# seq__control_pad_03.net
KiCad netlist of a schematic drawn in EAGLE
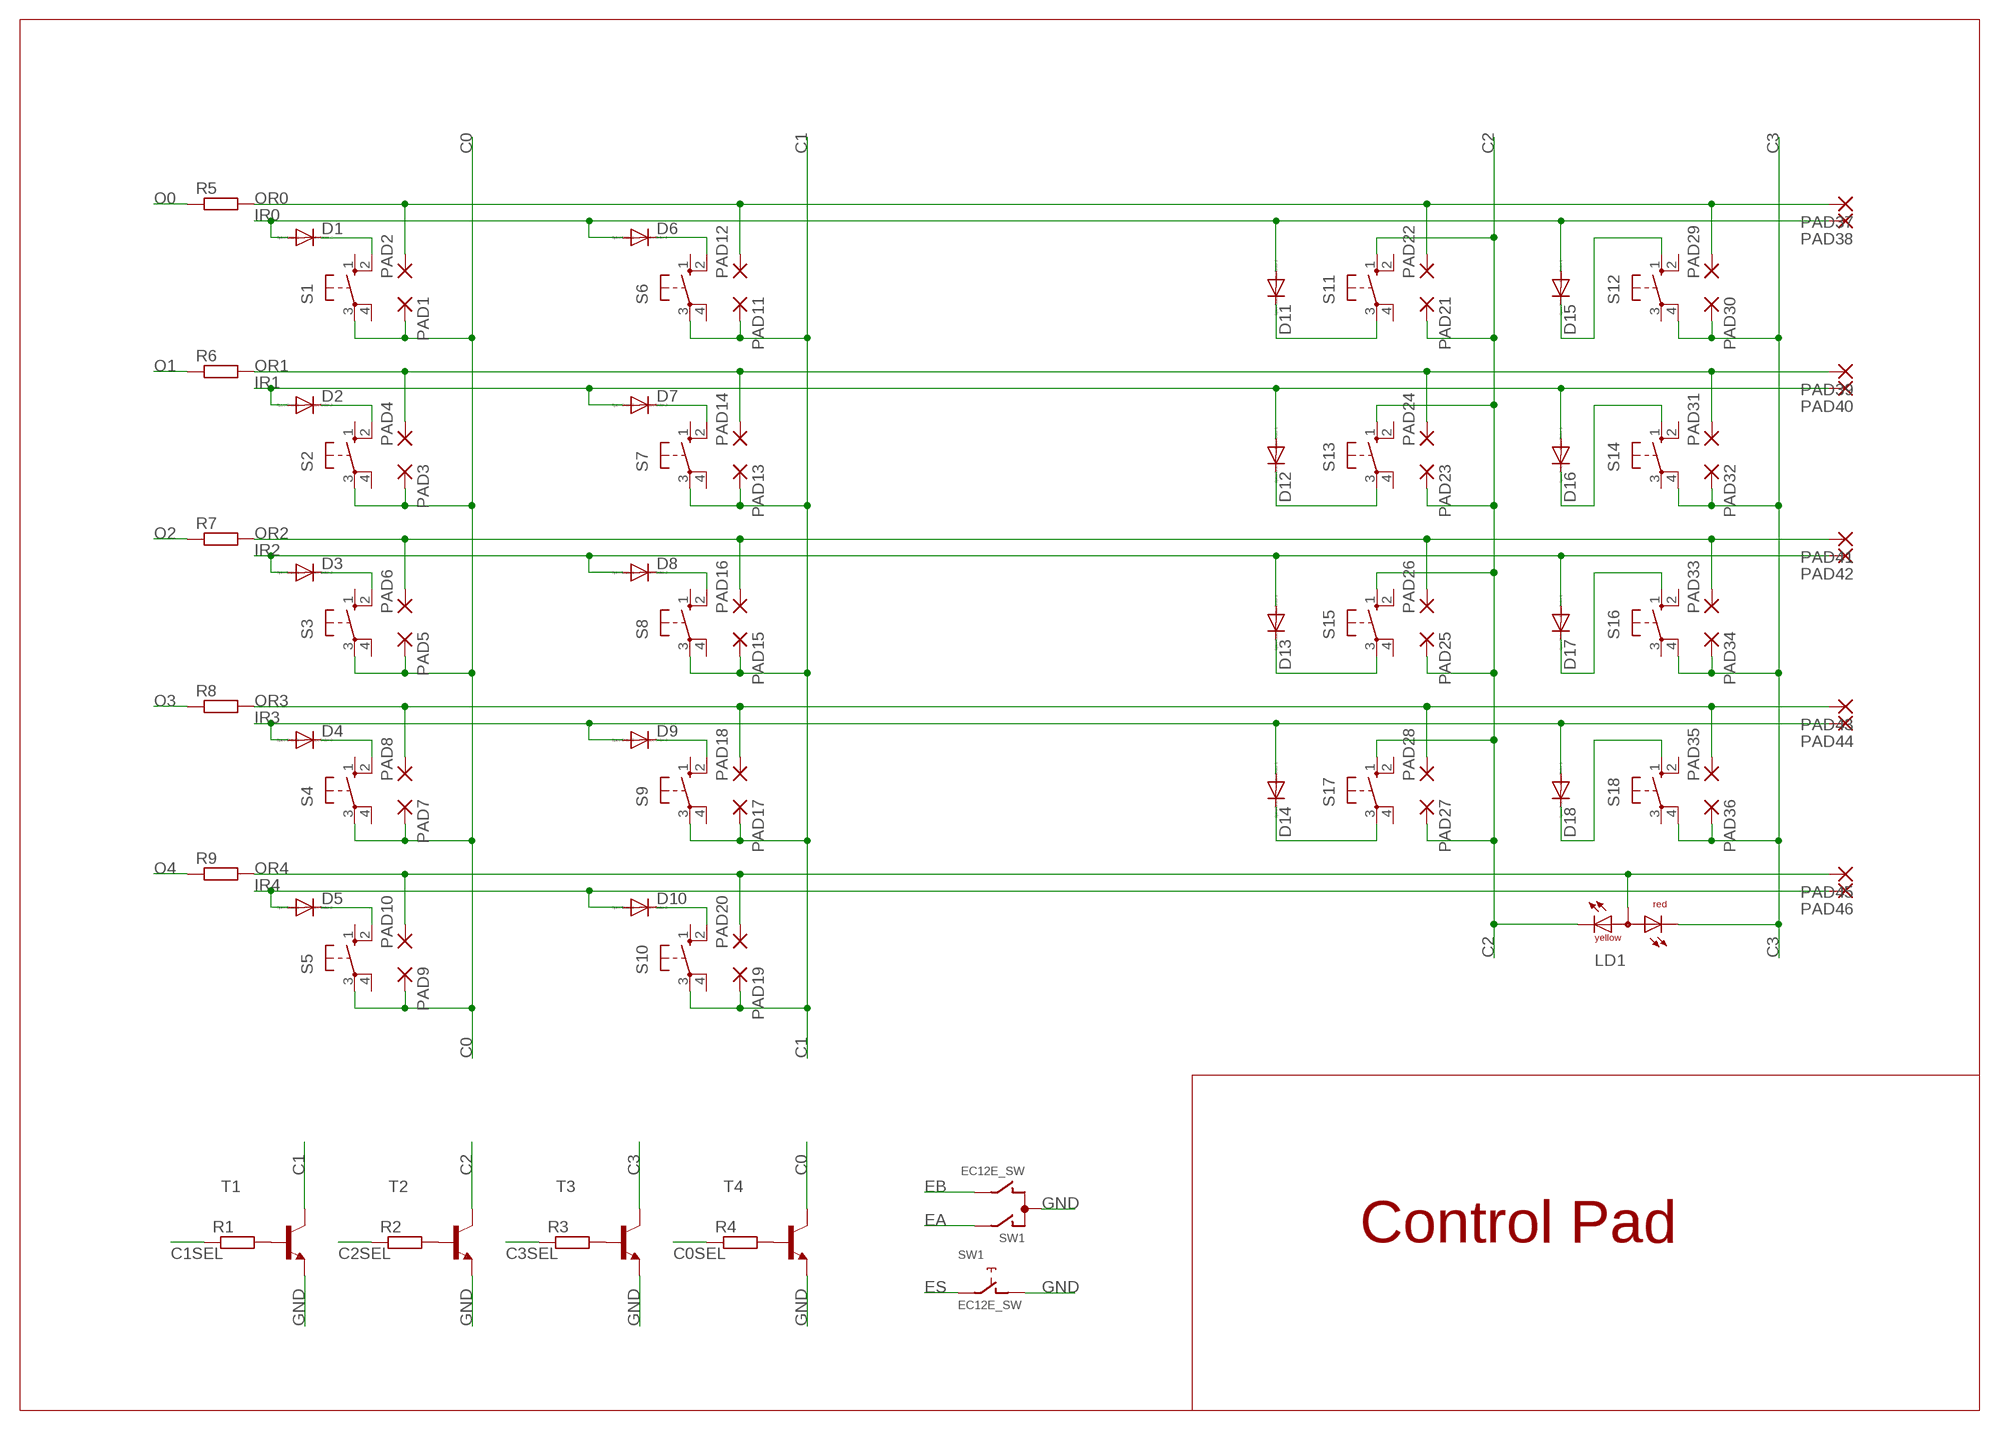
[diagram p0: schematic, sheet 1]
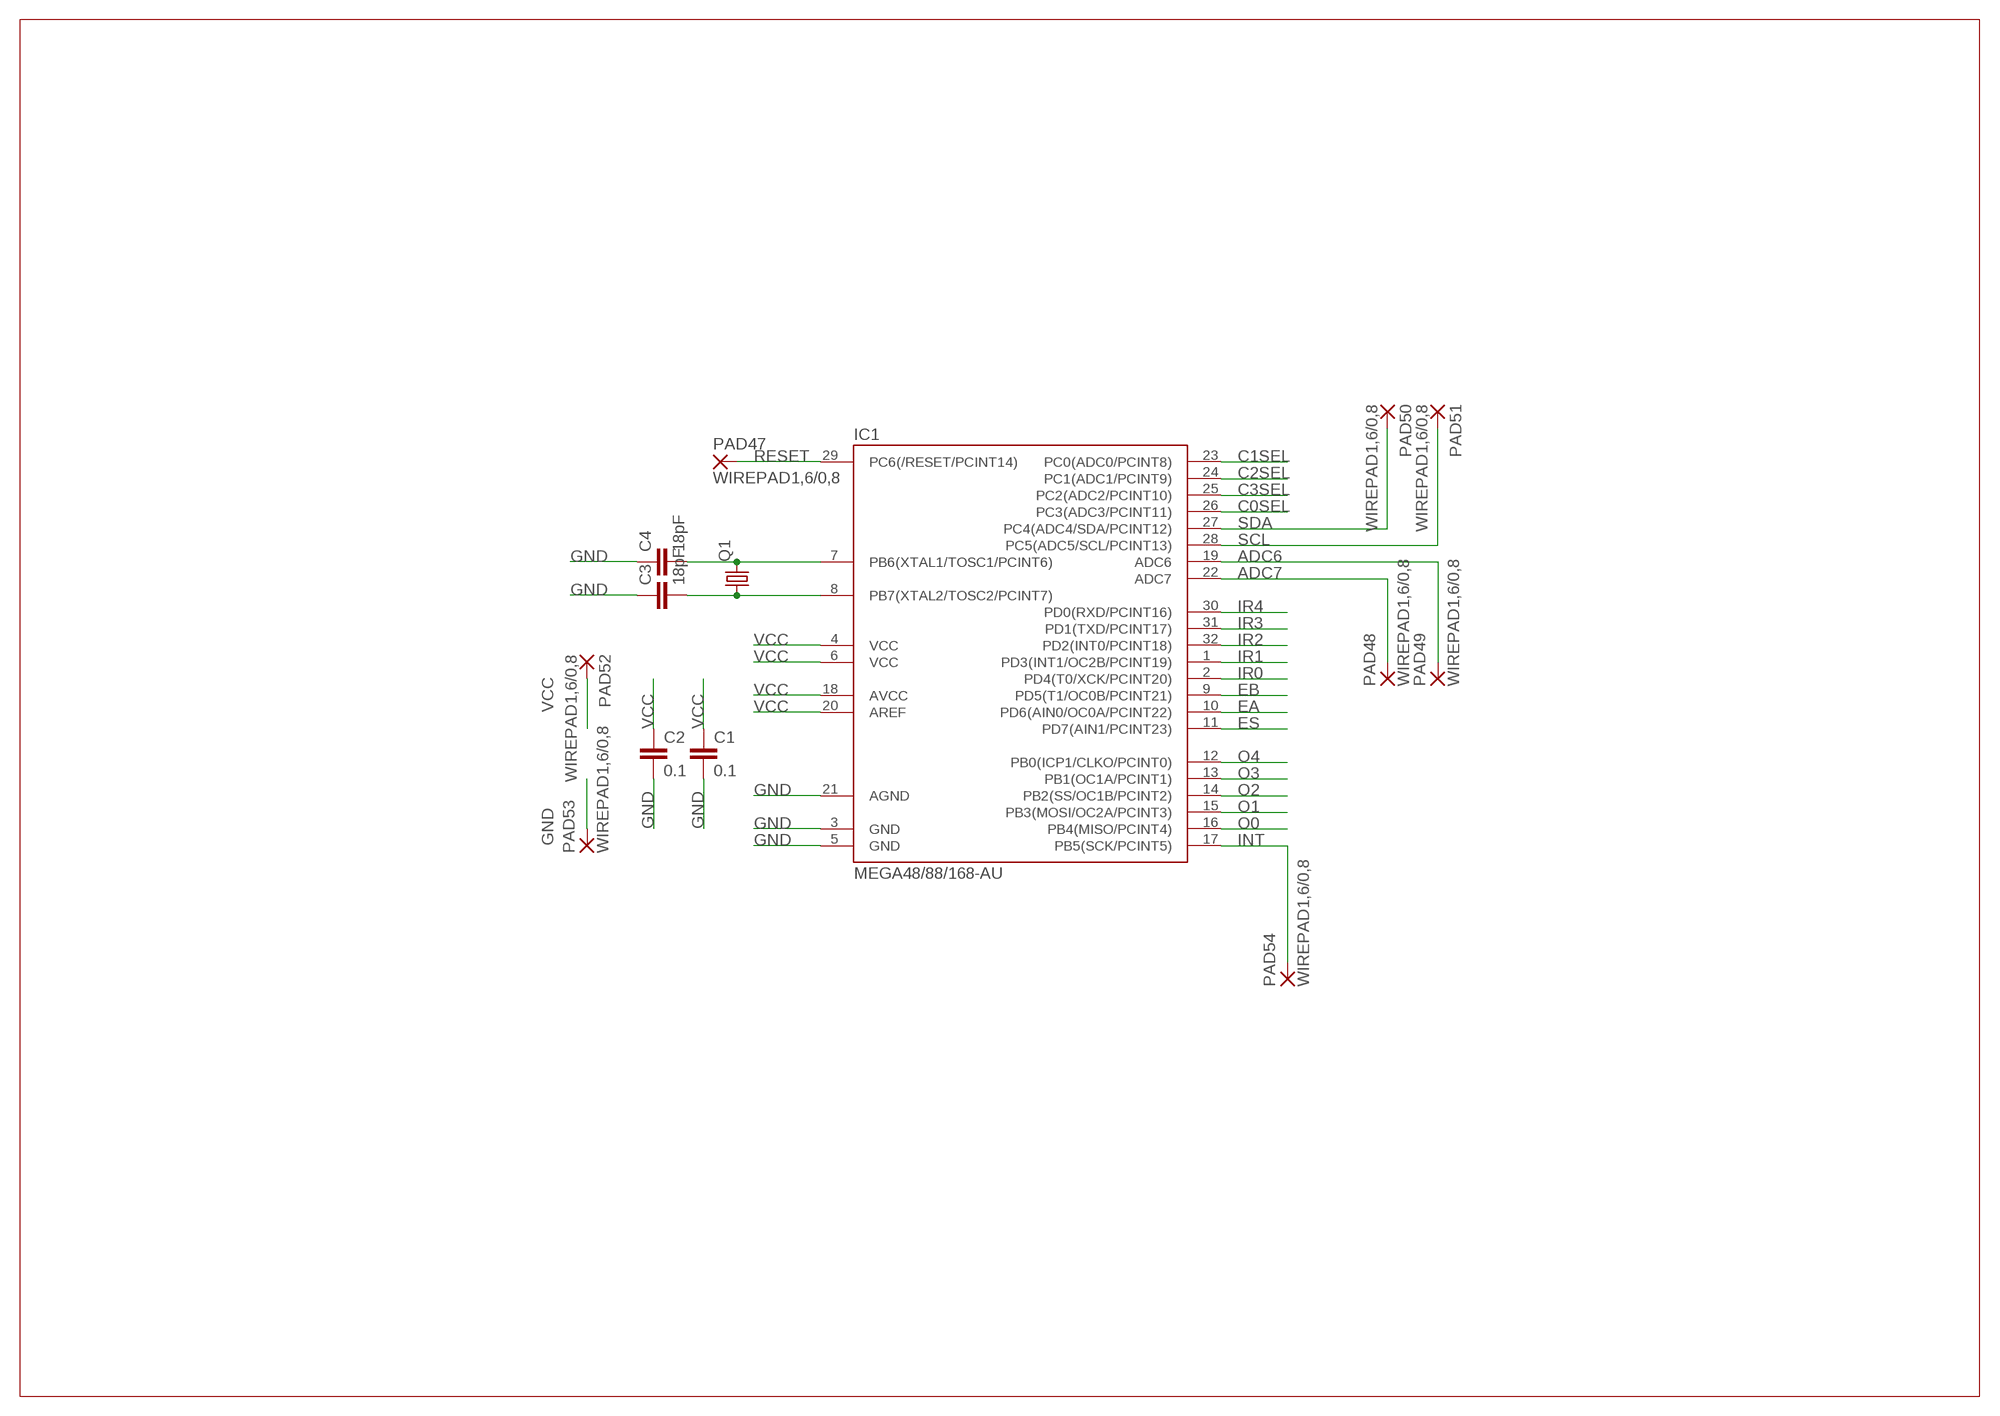
[diagram p1: schematic, sheet 2]

(export (version "E")
  (design (tool "Eeschema 10.0.6"))
  (components
    (comp (ref "C1")
      (value "0.1")
      (footprint "eagle-import:C0805")
      (libsource (lib "eagle-import") (part "C-EUC0805"))
    )
    (comp (ref "C2")
      (value "0.1")
      (footprint "eagle-import:C0805")
      (libsource (lib "eagle-import") (part "C-EUC0805"))
    )
    (comp (ref "C3")
      (value "18pF")
      (footprint "eagle-import:C0805")
      (libsource (lib "eagle-import") (part "C-EUC0805"))
    )
    (comp (ref "C4")
      (value "18pF")
      (footprint "eagle-import:C0805")
      (libsource (lib "eagle-import") (part "C-EUC0805"))
    )
    (comp (ref "IC1")
      (value "MEGA48/88/168-AU")
      (footprint "eagle-import:TQFP32-08")
      (libsource (lib "eagle-import") (part "MEGA48/88/168-AU"))
    )
    (comp (ref "PAD47")
      (value "WIREPAD1,6/0,8")
      (footprint "eagle-import:1,6_0,8")
      (libsource (lib "eagle-import") (part "WIREPAD1,6/0,8"))
    )
    (comp (ref "PAD48")
      (value "WIREPAD1,6/0,8")
      (footprint "eagle-import:1,6_0,8")
      (libsource (lib "eagle-import") (part "WIREPAD1,6/0,8"))
    )
    (comp (ref "PAD49")
      (value "WIREPAD1,6/0,8")
      (footprint "eagle-import:1,6_0,8")
      (libsource (lib "eagle-import") (part "WIREPAD1,6/0,8"))
    )
    (comp (ref "PAD50")
      (value "WIREPAD1,6/0,8")
      (footprint "eagle-import:1,6_0,8")
      (libsource (lib "eagle-import") (part "WIREPAD1,6/0,8"))
    )
    (comp (ref "PAD51")
      (value "WIREPAD1,6/0,8")
      (footprint "eagle-import:1,6_0,8")
      (libsource (lib "eagle-import") (part "WIREPAD1,6/0,8"))
    )
    (comp (ref "PAD52")
      (value "WIREPAD1,6/0,8")
      (footprint "eagle-import:1,6_0,8")
      (libsource (lib "eagle-import") (part "WIREPAD1,6/0,8"))
    )
    (comp (ref "PAD53")
      (value "WIREPAD1,6/0,8")
      (footprint "eagle-import:1,6_0,8")
      (libsource (lib "eagle-import") (part "WIREPAD1,6/0,8"))
    )
    (comp (ref "PAD54")
      (value "WIREPAD1,6/0,8")
      (footprint "eagle-import:1,6_0,8")
      (libsource (lib "eagle-import") (part "WIREPAD1,6/0,8"))
    )
    (comp (ref "Q1")
      (value "CRYSTALHC49S")
      (footprint "eagle-import:HC49_S")
      (libsource (lib "eagle-import") (part "CRYSTALHC49S"))
    )
    (comp (ref "D1")
      (value "DIODE-MINIMELF")
      (footprint "eagle-import:MINIMELF")
      (libsource (lib "eagle-import") (part "DIODE-MINIMELF"))
    )
    (comp (ref "D2")
      (value "DIODE-MINIMELF")
      (footprint "eagle-import:MINIMELF")
      (libsource (lib "eagle-import") (part "DIODE-MINIMELF"))
    )
    (comp (ref "D3")
      (value "DIODE-MINIMELF")
      (footprint "eagle-import:MINIMELF")
      (libsource (lib "eagle-import") (part "DIODE-MINIMELF"))
    )
    (comp (ref "D4")
      (value "DIODE-MINIMELF")
      (footprint "eagle-import:MINIMELF")
      (libsource (lib "eagle-import") (part "DIODE-MINIMELF"))
    )
    (comp (ref "D5")
      (value "DIODE-MINIMELF")
      (footprint "eagle-import:MINIMELF")
      (libsource (lib "eagle-import") (part "DIODE-MINIMELF"))
    )
    (comp (ref "D6")
      (value "DIODE-MINIMELF")
      (footprint "eagle-import:MINIMELF")
      (libsource (lib "eagle-import") (part "DIODE-MINIMELF"))
    )
    (comp (ref "D7")
      (value "DIODE-MINIMELF")
      (footprint "eagle-import:MINIMELF")
      (libsource (lib "eagle-import") (part "DIODE-MINIMELF"))
    )
    (comp (ref "D8")
      (value "DIODE-MINIMELF")
      (footprint "eagle-import:MINIMELF")
      (libsource (lib "eagle-import") (part "DIODE-MINIMELF"))
    )
    (comp (ref "D9")
      (value "DIODE-MINIMELF")
      (footprint "eagle-import:MINIMELF")
      (libsource (lib "eagle-import") (part "DIODE-MINIMELF"))
    )
    (comp (ref "D10")
      (value "DIODE-MINIMELF")
      (footprint "eagle-import:MINIMELF")
      (libsource (lib "eagle-import") (part "DIODE-MINIMELF"))
    )
    (comp (ref "D11")
      (value "DIODE-MINIMELF")
      (footprint "eagle-import:MINIMELF")
      (libsource (lib "eagle-import") (part "DIODE-MINIMELF"))
    )
    (comp (ref "D12")
      (value "DIODE-MINIMELF")
      (footprint "eagle-import:MINIMELF")
      (libsource (lib "eagle-import") (part "DIODE-MINIMELF"))
    )
    (comp (ref "D13")
      (value "DIODE-MINIMELF")
      (footprint "eagle-import:MINIMELF")
      (libsource (lib "eagle-import") (part "DIODE-MINIMELF"))
    )
    (comp (ref "D14")
      (value "DIODE-MINIMELF")
      (footprint "eagle-import:MINIMELF")
      (libsource (lib "eagle-import") (part "DIODE-MINIMELF"))
    )
    (comp (ref "D15")
      (value "DIODE-MINIMELF")
      (footprint "eagle-import:MINIMELF")
      (libsource (lib "eagle-import") (part "DIODE-MINIMELF"))
    )
    (comp (ref "D16")
      (value "DIODE-MINIMELF")
      (footprint "eagle-import:MINIMELF")
      (libsource (lib "eagle-import") (part "DIODE-MINIMELF"))
    )
    (comp (ref "D17")
      (value "DIODE-MINIMELF")
      (footprint "eagle-import:MINIMELF")
      (libsource (lib "eagle-import") (part "DIODE-MINIMELF"))
    )
    (comp (ref "D18")
      (value "DIODE-MINIMELF")
      (footprint "eagle-import:MINIMELF")
      (libsource (lib "eagle-import") (part "DIODE-MINIMELF"))
    )
    (comp (ref "LD1")
      (value "DUOLED-RY-A")
      (footprint "eagle-import:DUOLED-A-5MM")
      (libsource (lib "eagle-import") (part "DUOLED-RY-A"))
    )
    (comp (ref "PAD1")
      (value "1,6/0,8")
      (footprint "eagle-import:1,6_0,8")
      (libsource (lib "eagle-import") (part "1,6/0,8"))
    )
    (comp (ref "PAD2")
      (value "1,6/0,8")
      (footprint "eagle-import:1,6_0,8")
      (libsource (lib "eagle-import") (part "1,6/0,8"))
    )
    (comp (ref "PAD3")
      (value "1,6/0,8")
      (footprint "eagle-import:1,6_0,8")
      (libsource (lib "eagle-import") (part "1,6/0,8"))
    )
    (comp (ref "PAD4")
      (value "1,6/0,8")
      (footprint "eagle-import:1,6_0,8")
      (libsource (lib "eagle-import") (part "1,6/0,8"))
    )
    (comp (ref "PAD5")
      (value "1,6/0,8")
      (footprint "eagle-import:1,6_0,8")
      (libsource (lib "eagle-import") (part "1,6/0,8"))
    )
    (comp (ref "PAD6")
      (value "1,6/0,8")
      (footprint "eagle-import:1,6_0,8")
      (libsource (lib "eagle-import") (part "1,6/0,8"))
    )
    (comp (ref "PAD7")
      (value "1,6/0,8")
      (footprint "eagle-import:1,6_0,8")
      (libsource (lib "eagle-import") (part "1,6/0,8"))
    )
    (comp (ref "PAD8")
      (value "1,6/0,8")
      (footprint "eagle-import:1,6_0,8")
      (libsource (lib "eagle-import") (part "1,6/0,8"))
    )
    (comp (ref "PAD9")
      (value "1,6/0,8")
      (footprint "eagle-import:1,6_0,8")
      (libsource (lib "eagle-import") (part "1,6/0,8"))
    )
    (comp (ref "PAD10")
      (value "1,6/0,8")
      (footprint "eagle-import:1,6_0,8")
      (libsource (lib "eagle-import") (part "1,6/0,8"))
    )
    (comp (ref "PAD11")
      (value "1,6/0,8")
      (footprint "eagle-import:1,6_0,8")
      (libsource (lib "eagle-import") (part "1,6/0,8"))
    )
    (comp (ref "PAD12")
      (value "1,6/0,8")
      (footprint "eagle-import:1,6_0,8")
      (libsource (lib "eagle-import") (part "1,6/0,8"))
    )
    (comp (ref "PAD13")
      (value "1,6/0,8")
      (footprint "eagle-import:1,6_0,8")
      (libsource (lib "eagle-import") (part "1,6/0,8"))
    )
    (comp (ref "PAD14")
      (value "1,6/0,8")
      (footprint "eagle-import:1,6_0,8")
      (libsource (lib "eagle-import") (part "1,6/0,8"))
    )
    (comp (ref "PAD15")
      (value "1,6/0,8")
      (footprint "eagle-import:1,6_0,8")
      (libsource (lib "eagle-import") (part "1,6/0,8"))
    )
    (comp (ref "PAD16")
      (value "1,6/0,8")
      (footprint "eagle-import:1,6_0,8")
      (libsource (lib "eagle-import") (part "1,6/0,8"))
    )
    (comp (ref "PAD17")
      (value "1,6/0,8")
      (footprint "eagle-import:1,6_0,8")
      (libsource (lib "eagle-import") (part "1,6/0,8"))
    )
    (comp (ref "PAD18")
      (value "1,6/0,8")
      (footprint "eagle-import:1,6_0,8")
      (libsource (lib "eagle-import") (part "1,6/0,8"))
    )
    (comp (ref "PAD19")
      (value "1,6/0,8")
      (footprint "eagle-import:1,6_0,8")
      (libsource (lib "eagle-import") (part "1,6/0,8"))
    )
    (comp (ref "PAD20")
      (value "1,6/0,8")
      (footprint "eagle-import:1,6_0,8")
      (libsource (lib "eagle-import") (part "1,6/0,8"))
    )
    (comp (ref "PAD21")
      (value "1,6/0,8")
      (footprint "eagle-import:1,6_0,8")
      (libsource (lib "eagle-import") (part "1,6/0,8"))
    )
    (comp (ref "PAD22")
      (value "1,6/0,8")
      (footprint "eagle-import:1,6_0,8")
      (libsource (lib "eagle-import") (part "1,6/0,8"))
    )
    (comp (ref "PAD23")
      (value "1,6/0,8")
      (footprint "eagle-import:1,6_0,8")
      (libsource (lib "eagle-import") (part "1,6/0,8"))
    )
    (comp (ref "PAD24")
      (value "1,6/0,8")
      (footprint "eagle-import:1,6_0,8")
      (libsource (lib "eagle-import") (part "1,6/0,8"))
    )
    (comp (ref "PAD25")
      (value "1,6/0,8")
      (footprint "eagle-import:1,6_0,8")
      (libsource (lib "eagle-import") (part "1,6/0,8"))
    )
    (comp (ref "PAD26")
      (value "1,6/0,8")
      (footprint "eagle-import:1,6_0,8")
      (libsource (lib "eagle-import") (part "1,6/0,8"))
    )
    (comp (ref "PAD27")
      (value "1,6/0,8")
      (footprint "eagle-import:1,6_0,8")
      (libsource (lib "eagle-import") (part "1,6/0,8"))
    )
    (comp (ref "PAD28")
      (value "1,6/0,8")
      (footprint "eagle-import:1,6_0,8")
      (libsource (lib "eagle-import") (part "1,6/0,8"))
    )
    (comp (ref "PAD29")
      (value "1,6/0,8")
      (footprint "eagle-import:1,6_0,8")
      (libsource (lib "eagle-import") (part "1,6/0,8"))
    )
    (comp (ref "PAD30")
      (value "1,6/0,8")
      (footprint "eagle-import:1,6_0,8")
      (libsource (lib "eagle-import") (part "1,6/0,8"))
    )
    (comp (ref "PAD31")
      (value "1,6/0,8")
      (footprint "eagle-import:1,6_0,8")
      (libsource (lib "eagle-import") (part "1,6/0,8"))
    )
    (comp (ref "PAD32")
      (value "1,6/0,8")
      (footprint "eagle-import:1,6_0,8")
      (libsource (lib "eagle-import") (part "1,6/0,8"))
    )
    (comp (ref "PAD33")
      (value "1,6/0,8")
      (footprint "eagle-import:1,6_0,8")
      (libsource (lib "eagle-import") (part "1,6/0,8"))
    )
    (comp (ref "PAD34")
      (value "1,6/0,8")
      (footprint "eagle-import:1,6_0,8")
      (libsource (lib "eagle-import") (part "1,6/0,8"))
    )
    (comp (ref "PAD35")
      (value "1,6/0,8")
      (footprint "eagle-import:1,6_0,8")
      (libsource (lib "eagle-import") (part "1,6/0,8"))
    )
    (comp (ref "PAD36")
      (value "1,6/0,8")
      (footprint "eagle-import:1,6_0,8")
      (libsource (lib "eagle-import") (part "1,6/0,8"))
    )
    (comp (ref "PAD37")
      (value "1,6/0,8")
      (footprint "eagle-import:1,6_0,8")
      (libsource (lib "eagle-import") (part "1,6/0,8"))
    )
    (comp (ref "PAD38")
      (value "1,6/0,8")
      (footprint "eagle-import:1,6_0,8")
      (libsource (lib "eagle-import") (part "1,6/0,8"))
    )
    (comp (ref "PAD39")
      (value "1,6/0,8")
      (footprint "eagle-import:1,6_0,8")
      (libsource (lib "eagle-import") (part "1,6/0,8"))
    )
    (comp (ref "PAD40")
      (value "1,6/0,8")
      (footprint "eagle-import:1,6_0,8")
      (libsource (lib "eagle-import") (part "1,6/0,8"))
    )
    (comp (ref "PAD41")
      (value "1,6/0,8")
      (footprint "eagle-import:1,6_0,8")
      (libsource (lib "eagle-import") (part "1,6/0,8"))
    )
    (comp (ref "PAD42")
      (value "1,6/0,8")
      (footprint "eagle-import:1,6_0,8")
      (libsource (lib "eagle-import") (part "1,6/0,8"))
    )
    (comp (ref "PAD43")
      (value "1,6/0,8")
      (footprint "eagle-import:1,6_0,8")
      (libsource (lib "eagle-import") (part "1,6/0,8"))
    )
    (comp (ref "PAD44")
      (value "1,6/0,8")
      (footprint "eagle-import:1,6_0,8")
      (libsource (lib "eagle-import") (part "1,6/0,8"))
    )
    (comp (ref "PAD45")
      (value "1,6/0,8")
      (footprint "eagle-import:1,6_0,8")
      (libsource (lib "eagle-import") (part "1,6/0,8"))
    )
    (comp (ref "PAD46")
      (value "1,6/0,8")
      (footprint "eagle-import:1,6_0,8")
      (libsource (lib "eagle-import") (part "1,6/0,8"))
    )
    (comp (ref "R1")
      (value "R-EU_R0805")
      (footprint "eagle-import:R0805")
      (libsource (lib "eagle-import") (part "R-EU_R0805"))
    )
    (comp (ref "R2")
      (value "R-EU_R0805")
      (footprint "eagle-import:R0805")
      (libsource (lib "eagle-import") (part "R-EU_R0805"))
    )
    (comp (ref "R3")
      (value "R-EU_R0805")
      (footprint "eagle-import:R0805")
      (libsource (lib "eagle-import") (part "R-EU_R0805"))
    )
    (comp (ref "R4")
      (value "R-EU_R0805")
      (footprint "eagle-import:R0805")
      (libsource (lib "eagle-import") (part "R-EU_R0805"))
    )
    (comp (ref "R5")
      (value "R-EU_R0805")
      (footprint "eagle-import:R0805")
      (libsource (lib "eagle-import") (part "R-EU_R0805"))
    )
    (comp (ref "R6")
      (value "R-EU_R0805")
      (footprint "eagle-import:R0805")
      (libsource (lib "eagle-import") (part "R-EU_R0805"))
    )
    (comp (ref "R7")
      (value "R-EU_R0805")
      (footprint "eagle-import:R0805")
      (libsource (lib "eagle-import") (part "R-EU_R0805"))
    )
    (comp (ref "R8")
      (value "R-EU_R0805")
      (footprint "eagle-import:R0805")
      (libsource (lib "eagle-import") (part "R-EU_R0805"))
    )
    (comp (ref "R9")
      (value "R-EU_R0805")
      (footprint "eagle-import:R0805")
      (libsource (lib "eagle-import") (part "R-EU_R0805"))
    )
    (comp (ref "S1")
      (value "40-XX")
      (footprint "eagle-import:B3F-40XX")
      (fields (field (name "MF") "OMRON COMPONENTS USA") (field (name "MPN") "B3F-4000"))
      (libsource (lib "eagle-import") (part "40-XX"))
    )
    (comp (ref "S2")
      (value "40-XX")
      (footprint "eagle-import:B3F-40XX")
      (fields (field (name "MF") "OMRON COMPONENTS USA") (field (name "MPN") "B3F-4000"))
      (libsource (lib "eagle-import") (part "40-XX"))
    )
    (comp (ref "S3")
      (value "40-XX")
      (footprint "eagle-import:B3F-40XX")
      (fields (field (name "MF") "OMRON COMPONENTS USA") (field (name "MPN") "B3F-4000"))
      (libsource (lib "eagle-import") (part "40-XX"))
    )
    (comp (ref "S4")
      (value "40-XX")
      (footprint "eagle-import:B3F-40XX")
      (fields (field (name "MF") "OMRON COMPONENTS USA") (field (name "MPN") "B3F-4000"))
      (libsource (lib "eagle-import") (part "40-XX"))
    )
    (comp (ref "S5")
      (value "40-XX")
      (footprint "eagle-import:B3F-40XX")
      (fields (field (name "MF") "OMRON COMPONENTS USA") (field (name "MPN") "B3F-4000"))
      (libsource (lib "eagle-import") (part "40-XX"))
    )
    (comp (ref "S6")
      (value "40-XX")
      (footprint "eagle-import:B3F-40XX")
      (fields (field (name "MF") "OMRON COMPONENTS USA") (field (name "MPN") "B3F-4000"))
      (libsource (lib "eagle-import") (part "40-XX"))
    )
    (comp (ref "S7")
      (value "40-XX")
      (footprint "eagle-import:B3F-40XX")
      (fields (field (name "MF") "OMRON COMPONENTS USA") (field (name "MPN") "B3F-4000"))
      (libsource (lib "eagle-import") (part "40-XX"))
    )
    (comp (ref "S8")
      (value "40-XX")
      (footprint "eagle-import:B3F-40XX")
      (fields (field (name "MF") "OMRON COMPONENTS USA") (field (name "MPN") "B3F-4000"))
      (libsource (lib "eagle-import") (part "40-XX"))
    )
    (comp (ref "S9")
      (value "40-XX")
      (footprint "eagle-import:B3F-40XX")
      (fields (field (name "MF") "OMRON COMPONENTS USA") (field (name "MPN") "B3F-4000"))
      (libsource (lib "eagle-import") (part "40-XX"))
    )
    (comp (ref "S10")
      (value "40-XX")
      (footprint "eagle-import:B3F-40XX")
      (fields (field (name "MF") "OMRON COMPONENTS USA") (field (name "MPN") "B3F-4000"))
      (libsource (lib "eagle-import") (part "40-XX"))
    )
    (comp (ref "S11")
      (value "40-XX")
      (footprint "eagle-import:B3F-40XX")
      (fields (field (name "MF") "OMRON COMPONENTS USA") (field (name "MPN") "B3F-4000"))
      (libsource (lib "eagle-import") (part "40-XX"))
    )
    (comp (ref "S12")
      (value "40-XX")
      (footprint "eagle-import:B3F-40XX")
      (fields (field (name "MF") "OMRON COMPONENTS USA") (field (name "MPN") "B3F-4000"))
      (libsource (lib "eagle-import") (part "40-XX"))
    )
    (comp (ref "S13")
      (value "40-XX")
      (footprint "eagle-import:B3F-40XX")
      (fields (field (name "MF") "OMRON COMPONENTS USA") (field (name "MPN") "B3F-4000"))
      (libsource (lib "eagle-import") (part "40-XX"))
    )
    (comp (ref "S14")
      (value "40-XX")
      (footprint "eagle-import:B3F-40XX")
      (fields (field (name "MF") "OMRON COMPONENTS USA") (field (name "MPN") "B3F-4000"))
      (libsource (lib "eagle-import") (part "40-XX"))
    )
    (comp (ref "S15")
      (value "40-XX")
      (footprint "eagle-import:B3F-40XX")
      (fields (field (name "MF") "OMRON COMPONENTS USA") (field (name "MPN") "B3F-4000"))
      (libsource (lib "eagle-import") (part "40-XX"))
    )
    (comp (ref "S16")
      (value "40-XX")
      (footprint "eagle-import:B3F-40XX")
      (fields (field (name "MF") "OMRON COMPONENTS USA") (field (name "MPN") "B3F-4000"))
      (libsource (lib "eagle-import") (part "40-XX"))
    )
    (comp (ref "S17")
      (value "40-XX")
      (footprint "eagle-import:B3F-40XX")
      (fields (field (name "MF") "OMRON COMPONENTS USA") (field (name "MPN") "B3F-4000"))
      (libsource (lib "eagle-import") (part "40-XX"))
    )
    (comp (ref "S18")
      (value "40-XX")
      (footprint "eagle-import:B3F-40XX")
      (fields (field (name "MF") "OMRON COMPONENTS USA") (field (name "MPN") "B3F-4000"))
      (libsource (lib "eagle-import") (part "40-XX"))
    )
    (comp (ref "SW1")
      (value "EC12E_SW")
      (footprint "eagle-import:ALPS_EC12E_SW")
      (fields (field (name "MPN") "EC12E2424407"))
      (libsource (lib "eagle-import") (part "EC12E_SW"))
    )
    (comp (ref "T1")
      (value "MMBT3904LT1-NPN-SOT23-BEC")
      (footprint "eagle-import:SOT23-BEC")
      (libsource (lib "eagle-import") (part "-NPN-SOT23-BECMMBT3904LT1"))
    )
    (comp (ref "T2")
      (value "MMBT3904LT1-NPN-SOT23-BEC")
      (footprint "eagle-import:SOT23-BEC")
      (libsource (lib "eagle-import") (part "-NPN-SOT23-BECMMBT3904LT1"))
    )
    (comp (ref "T3")
      (value "MMBT3904LT1-NPN-SOT23-BEC")
      (footprint "eagle-import:SOT23-BEC")
      (libsource (lib "eagle-import") (part "-NPN-SOT23-BECMMBT3904LT1"))
    )
    (comp (ref "T4")
      (value "MMBT3904LT1-NPN-SOT23-BEC")
      (footprint "eagle-import:SOT23-BEC")
      (libsource (lib "eagle-import") (part "-NPN-SOT23-BECMMBT3904LT1"))
    )
  )
  (nets
    (net (code "1") (name "ADC6") (class "Default")
      (node (ref "IC1") (pin "19") (pinfunction "ADC6_19") (pintype "passive"))
      (node (ref "PAD49") (pin "1") (pinfunction "P_1") (pintype "passive"))
    )
    (net (code "2") (name "ADC7") (class "Default")
      (node (ref "IC1") (pin "22") (pinfunction "ADC7_22") (pintype "passive"))
      (node (ref "PAD48") (pin "1") (pinfunction "P_1") (pintype "passive"))
    )
    (net (code "3") (name "C0") (class "Default")
      (node (ref "PAD1") (pin "1") (pinfunction "P_1") (pintype "passive"))
      (node (ref "PAD3") (pin "1") (pinfunction "P_1") (pintype "passive"))
      (node (ref "PAD5") (pin "1") (pinfunction "P_1") (pintype "passive"))
      (node (ref "PAD7") (pin "1") (pinfunction "P_1") (pintype "passive"))
      (node (ref "PAD9") (pin "1") (pinfunction "P_1") (pintype "passive"))
      (node (ref "S1") (pin "3") (pinfunction "P_3") (pintype "passive"))
      (node (ref "S2") (pin "3") (pinfunction "P_3") (pintype "passive"))
      (node (ref "S3") (pin "3") (pinfunction "P_3") (pintype "passive"))
      (node (ref "S4") (pin "3") (pinfunction "P_3") (pintype "passive"))
      (node (ref "S5") (pin "3") (pinfunction "P_3") (pintype "passive"))
      (node (ref "T4") (pin "C") (pinfunction "C_C") (pintype "passive"))
    )
    (net (code "4") (name "C0SEL") (class "Default")
      (node (ref "IC1") (pin "26") (pinfunction "PC3(ADC3/PCINT11)_26") (pintype "bidirectional"))
      (node (ref "R4") (pin "1") (pinfunction "1_1") (pintype "passive"))
    )
    (net (code "5") (name "C1") (class "Default")
      (node (ref "PAD11") (pin "1") (pinfunction "P_1") (pintype "passive"))
      (node (ref "PAD13") (pin "1") (pinfunction "P_1") (pintype "passive"))
      (node (ref "PAD15") (pin "1") (pinfunction "P_1") (pintype "passive"))
      (node (ref "PAD17") (pin "1") (pinfunction "P_1") (pintype "passive"))
      (node (ref "PAD19") (pin "1") (pinfunction "P_1") (pintype "passive"))
      (node (ref "S10") (pin "3") (pinfunction "P_3") (pintype "passive"))
      (node (ref "S6") (pin "3") (pinfunction "P_3") (pintype "passive"))
      (node (ref "S7") (pin "3") (pinfunction "P_3") (pintype "passive"))
      (node (ref "S8") (pin "3") (pinfunction "P_3") (pintype "passive"))
      (node (ref "S9") (pin "3") (pinfunction "P_3") (pintype "passive"))
      (node (ref "T1") (pin "C") (pinfunction "C_C") (pintype "passive"))
    )
    (net (code "6") (name "C1SEL") (class "Default")
      (node (ref "IC1") (pin "23") (pinfunction "PC0(ADC0/PCINT8)_23") (pintype "bidirectional"))
      (node (ref "R1") (pin "1") (pinfunction "1_1") (pintype "passive"))
    )
    (net (code "7") (name "C2") (class "Default")
      (node (ref "LD1") (pin "CX") (pinfunction "CY_CX") (pintype "passive"))
      (node (ref "PAD21") (pin "1") (pinfunction "P_1") (pintype "passive"))
      (node (ref "PAD23") (pin "1") (pinfunction "P_1") (pintype "passive"))
      (node (ref "PAD25") (pin "1") (pinfunction "P_1") (pintype "passive"))
      (node (ref "PAD27") (pin "1") (pinfunction "P_1") (pintype "passive"))
      (node (ref "S11") (pin "1") (pinfunction "S_1") (pintype "passive"))
      (node (ref "S13") (pin "1") (pinfunction "S_1") (pintype "passive"))
      (node (ref "S15") (pin "1") (pinfunction "S_1") (pintype "passive"))
      (node (ref "S17") (pin "1") (pinfunction "S_1") (pintype "passive"))
      (node (ref "T2") (pin "C") (pinfunction "C_C") (pintype "passive"))
    )
    (net (code "8") (name "C2SEL") (class "Default")
      (node (ref "IC1") (pin "24") (pinfunction "PC1(ADC1/PCINT9)_24") (pintype "bidirectional"))
      (node (ref "R2") (pin "1") (pinfunction "1_1") (pintype "passive"))
    )
    (net (code "9") (name "C3") (class "Default")
      (node (ref "LD1") (pin "CR") (pinfunction "CR_CR") (pintype "passive"))
      (node (ref "PAD30") (pin "1") (pinfunction "P_1") (pintype "passive"))
      (node (ref "PAD32") (pin "1") (pinfunction "P_1") (pintype "passive"))
      (node (ref "PAD34") (pin "1") (pinfunction "P_1") (pintype "passive"))
      (node (ref "PAD36") (pin "1") (pinfunction "P_1") (pintype "passive"))
      (node (ref "S12") (pin "4") (pinfunction "P1_4") (pintype "passive"))
      (node (ref "S14") (pin "4") (pinfunction "P1_4") (pintype "passive"))
      (node (ref "S16") (pin "4") (pinfunction "P1_4") (pintype "passive"))
      (node (ref "S18") (pin "4") (pinfunction "P1_4") (pintype "passive"))
      (node (ref "T3") (pin "C") (pinfunction "C_C") (pintype "passive"))
    )
    (net (code "10") (name "C3SEL") (class "Default")
      (node (ref "IC1") (pin "25") (pinfunction "PC2(ADC2/PCINT10)_25") (pintype "bidirectional"))
      (node (ref "R3") (pin "1") (pinfunction "1_1") (pintype "passive"))
    )
    (net (code "11") (name "EA") (class "Default")
      (node (ref "IC1") (pin "10") (pinfunction "PD6(AIN0/OC0A/PCINT22)_10") (pintype "bidirectional"))
      (node (ref "SW1") (pin "A") (pinfunction "A_A") (pintype "passive"))
    )
    (net (code "12") (name "EB") (class "Default")
      (node (ref "IC1") (pin "9") (pinfunction "PD5(T1/OC0B/PCINT21)_9") (pintype "bidirectional"))
      (node (ref "SW1") (pin "B") (pinfunction "B_B") (pintype "passive"))
    )
    (net (code "13") (name "ES") (class "Default")
      (node (ref "IC1") (pin "11") (pinfunction "PD7(AIN1/PCINT23)_11") (pintype "bidirectional"))
      (node (ref "SW1") (pin "E") (pinfunction "2_E") (pintype "passive"))
    )
    (net (code "14") (name "GND") (class "Default")
      (node (ref "C1") (pin "2") (pinfunction "2_2") (pintype "passive"))
      (node (ref "C2") (pin "2") (pinfunction "2_2") (pintype "passive"))
      (node (ref "C3") (pin "1") (pinfunction "1_1") (pintype "passive"))
      (node (ref "C4") (pin "1") (pinfunction "1_1") (pintype "passive"))
      (node (ref "IC1") (pin "21") (pinfunction "AGND_21") (pintype "power_in"))
      (node (ref "IC1") (pin "3") (pinfunction "GND_3") (pintype "power_in"))
      (node (ref "IC1") (pin "5") (pinfunction "GND_5") (pintype "power_in"))
      (node (ref "PAD53") (pin "1") (pinfunction "P_1") (pintype "passive"))
      (node (ref "SW1") (pin "C") (pinfunction "C_C") (pintype "passive"))
      (node (ref "SW1") (pin "D") (pinfunction "1_D") (pintype "passive"))
      (node (ref "T1") (pin "E") (pinfunction "E_E") (pintype "passive"))
      (node (ref "T2") (pin "E") (pinfunction "E_E") (pintype "passive"))
      (node (ref "T3") (pin "E") (pinfunction "E_E") (pintype "passive"))
      (node (ref "T4") (pin "E") (pinfunction "E_E") (pintype "passive"))
    )
    (net (code "15") (name "INT") (class "Default")
      (node (ref "IC1") (pin "17") (pinfunction "PB5(SCK/PCINT5)_17") (pintype "bidirectional"))
      (node (ref "PAD54") (pin "1") (pinfunction "P_1") (pintype "passive"))
    )
    (net (code "16") (name "IR0") (class "Default")
      (node (ref "D1") (pin "A") (pinfunction "A_A") (pintype "passive"))
      (node (ref "D11") (pin "A") (pinfunction "A_A") (pintype "passive"))
      (node (ref "D15") (pin "A") (pinfunction "A_A") (pintype "passive"))
      (node (ref "D6") (pin "A") (pinfunction "A_A") (pintype "passive"))
      (node (ref "IC1") (pin "2") (pinfunction "PD4(T0/XCK/PCINT20)_2") (pintype "bidirectional"))
      (node (ref "PAD38") (pin "1") (pinfunction "P_1") (pintype "passive"))
    )
    (net (code "17") (name "IR1") (class "Default")
      (node (ref "D12") (pin "A") (pinfunction "A_A") (pintype "passive"))
      (node (ref "D16") (pin "A") (pinfunction "A_A") (pintype "passive"))
      (node (ref "D2") (pin "A") (pinfunction "A_A") (pintype "passive"))
      (node (ref "D7") (pin "A") (pinfunction "A_A") (pintype "passive"))
      (node (ref "IC1") (pin "1") (pinfunction "PD3(INT1/OC2B/PCINT19)_1") (pintype "bidirectional"))
      (node (ref "PAD40") (pin "1") (pinfunction "P_1") (pintype "passive"))
    )
    (net (code "18") (name "IR2") (class "Default")
      (node (ref "D13") (pin "A") (pinfunction "A_A") (pintype "passive"))
      (node (ref "D17") (pin "A") (pinfunction "A_A") (pintype "passive"))
      (node (ref "D3") (pin "A") (pinfunction "A_A") (pintype "passive"))
      (node (ref "D8") (pin "A") (pinfunction "A_A") (pintype "passive"))
      (node (ref "IC1") (pin "32") (pinfunction "PD2(INT0/PCINT18)_32") (pintype "bidirectional"))
      (node (ref "PAD42") (pin "1") (pinfunction "P_1") (pintype "passive"))
    )
    (net (code "19") (name "IR3") (class "Default")
      (node (ref "D14") (pin "A") (pinfunction "A_A") (pintype "passive"))
      (node (ref "D18") (pin "A") (pinfunction "A_A") (pintype "passive"))
      (node (ref "D4") (pin "A") (pinfunction "A_A") (pintype "passive"))
      (node (ref "D9") (pin "A") (pinfunction "A_A") (pintype "passive"))
      (node (ref "IC1") (pin "31") (pinfunction "PD1(TXD/PCINT17)_31") (pintype "bidirectional"))
      (node (ref "PAD44") (pin "1") (pinfunction "P_1") (pintype "passive"))
    )
    (net (code "20") (name "IR4") (class "Default")
      (node (ref "D10") (pin "A") (pinfunction "A_A") (pintype "passive"))
      (node (ref "D5") (pin "A") (pinfunction "A_A") (pintype "passive"))
      (node (ref "IC1") (pin "30") (pinfunction "PD0(RXD/PCINT16)_30") (pintype "bidirectional"))
      (node (ref "PAD46") (pin "1") (pinfunction "P_1") (pintype "passive"))
    )
    (net (code "21") (name "Net-(IC1-PB6(XTAL1{slash}TOSC1{slash}PCINT6))") (class "Default")
      (node (ref "C4") (pin "2") (pinfunction "2_2") (pintype "passive"))
      (node (ref "IC1") (pin "7") (pinfunction "PB6(XTAL1/TOSC1/PCINT6)_7") (pintype "bidirectional"))
      (node (ref "Q1") (pin "2") (pinfunction "2_2") (pintype "passive"))
    )
    (net (code "22") (name "Net-(IC1-PB7(XTAL2{slash}TOSC2{slash}PCINT7))") (class "Default")
      (node (ref "C3") (pin "2") (pinfunction "2_2") (pintype "passive"))
      (node (ref "IC1") (pin "8") (pinfunction "PB7(XTAL2/TOSC2/PCINT7)_8") (pintype "bidirectional"))
      (node (ref "Q1") (pin "1") (pinfunction "1_1") (pintype "passive"))
    )
    (net (code "23") (name "Net-(R1-Pad2)") (class "Default")
      (node (ref "R1") (pin "2") (pinfunction "2_2") (pintype "passive"))
      (node (ref "T1") (pin "B") (pinfunction "B_B") (pintype "passive"))
    )
    (net (code "24") (name "Net-(R2-Pad2)") (class "Default")
      (node (ref "R2") (pin "2") (pinfunction "2_2") (pintype "passive"))
      (node (ref "T2") (pin "B") (pinfunction "B_B") (pintype "passive"))
    )
    (net (code "25") (name "Net-(R3-Pad2)") (class "Default")
      (node (ref "R3") (pin "2") (pinfunction "2_2") (pintype "passive"))
      (node (ref "T3") (pin "B") (pinfunction "B_B") (pintype "passive"))
    )
    (net (code "26") (name "Net-(R4-Pad2)") (class "Default")
      (node (ref "R4") (pin "2") (pinfunction "2_2") (pintype "passive"))
      (node (ref "T4") (pin "B") (pinfunction "B_B") (pintype "passive"))
    )
    (net (code "27") (name "Net-(S1-S1)") (class "Default")
      (node (ref "D1") (pin "C") (pinfunction "C_C") (pintype "passive"))
      (node (ref "S1") (pin "2") (pinfunction "S1_2") (pintype "passive"))
    )
    (net (code "28") (name "Net-(S2-S1)") (class "Default")
      (node (ref "D2") (pin "C") (pinfunction "C_C") (pintype "passive"))
      (node (ref "S2") (pin "2") (pinfunction "S1_2") (pintype "passive"))
    )
    (net (code "29") (name "Net-(S3-S1)") (class "Default")
      (node (ref "D3") (pin "C") (pinfunction "C_C") (pintype "passive"))
      (node (ref "S3") (pin "2") (pinfunction "S1_2") (pintype "passive"))
    )
    (net (code "30") (name "Net-(S4-S1)") (class "Default")
      (node (ref "D4") (pin "C") (pinfunction "C_C") (pintype "passive"))
      (node (ref "S4") (pin "2") (pinfunction "S1_2") (pintype "passive"))
    )
    (net (code "31") (name "Net-(S5-S1)") (class "Default")
      (node (ref "D5") (pin "C") (pinfunction "C_C") (pintype "passive"))
      (node (ref "S5") (pin "2") (pinfunction "S1_2") (pintype "passive"))
    )
    (net (code "32") (name "Net-(S6-S1)") (class "Default")
      (node (ref "D6") (pin "C") (pinfunction "C_C") (pintype "passive"))
      (node (ref "S6") (pin "2") (pinfunction "S1_2") (pintype "passive"))
    )
    (net (code "33") (name "Net-(S7-S1)") (class "Default")
      (node (ref "D7") (pin "C") (pinfunction "C_C") (pintype "passive"))
      (node (ref "S7") (pin "2") (pinfunction "S1_2") (pintype "passive"))
    )
    (net (code "34") (name "Net-(S8-S1)") (class "Default")
      (node (ref "D8") (pin "C") (pinfunction "C_C") (pintype "passive"))
      (node (ref "S8") (pin "2") (pinfunction "S1_2") (pintype "passive"))
    )
    (net (code "35") (name "Net-(S9-S1)") (class "Default")
      (node (ref "D9") (pin "C") (pinfunction "C_C") (pintype "passive"))
      (node (ref "S9") (pin "2") (pinfunction "S1_2") (pintype "passive"))
    )
    (net (code "36") (name "Net-(S10-S1)") (class "Default")
      (node (ref "D10") (pin "C") (pinfunction "C_C") (pintype "passive"))
      (node (ref "S10") (pin "2") (pinfunction "S1_2") (pintype "passive"))
    )
    (net (code "37") (name "Net-(S11-P)") (class "Default")
      (node (ref "D11") (pin "C") (pinfunction "C_C") (pintype "passive"))
      (node (ref "S11") (pin "3") (pinfunction "P_3") (pintype "passive"))
    )
    (net (code "38") (name "Net-(S12-S)") (class "Default")
      (node (ref "D15") (pin "C") (pinfunction "C_C") (pintype "passive"))
      (node (ref "S12") (pin "1") (pinfunction "S_1") (pintype "passive"))
    )
    (net (code "39") (name "Net-(S13-P)") (class "Default")
      (node (ref "D12") (pin "C") (pinfunction "C_C") (pintype "passive"))
      (node (ref "S13") (pin "3") (pinfunction "P_3") (pintype "passive"))
    )
    (net (code "40") (name "Net-(S14-S)") (class "Default")
      (node (ref "D16") (pin "C") (pinfunction "C_C") (pintype "passive"))
      (node (ref "S14") (pin "1") (pinfunction "S_1") (pintype "passive"))
    )
    (net (code "41") (name "Net-(S15-P)") (class "Default")
      (node (ref "D13") (pin "C") (pinfunction "C_C") (pintype "passive"))
      (node (ref "S15") (pin "3") (pinfunction "P_3") (pintype "passive"))
    )
    (net (code "42") (name "Net-(S16-S)") (class "Default")
      (node (ref "D17") (pin "C") (pinfunction "C_C") (pintype "passive"))
      (node (ref "S16") (pin "1") (pinfunction "S_1") (pintype "passive"))
    )
    (net (code "43") (name "Net-(S17-P)") (class "Default")
      (node (ref "D14") (pin "C") (pinfunction "C_C") (pintype "passive"))
      (node (ref "S17") (pin "3") (pinfunction "P_3") (pintype "passive"))
    )
    (net (code "44") (name "Net-(S18-S)") (class "Default")
      (node (ref "D18") (pin "C") (pinfunction "C_C") (pintype "passive"))
      (node (ref "S18") (pin "1") (pinfunction "S_1") (pintype "passive"))
    )
    (net (code "45") (name "O0") (class "Default")
      (node (ref "IC1") (pin "16") (pinfunction "PB4(MISO/PCINT4)_16") (pintype "bidirectional"))
      (node (ref "R5") (pin "1") (pinfunction "1_1") (pintype "passive"))
    )
    (net (code "46") (name "O1") (class "Default")
      (node (ref "IC1") (pin "15") (pinfunction "PB3(MOSI/OC2A/PCINT3)_15") (pintype "bidirectional"))
      (node (ref "R6") (pin "1") (pinfunction "1_1") (pintype "passive"))
    )
    (net (code "47") (name "O2") (class "Default")
      (node (ref "IC1") (pin "14") (pinfunction "PB2(SS/OC1B/PCINT2)_14") (pintype "bidirectional"))
      (node (ref "R7") (pin "1") (pinfunction "1_1") (pintype "passive"))
    )
    (net (code "48") (name "O3") (class "Default")
      (node (ref "IC1") (pin "13") (pinfunction "PB1(OC1A/PCINT1)_13") (pintype "bidirectional"))
      (node (ref "R8") (pin "1") (pinfunction "1_1") (pintype "passive"))
    )
    (net (code "49") (name "O4") (class "Default")
      (node (ref "IC1") (pin "12") (pinfunction "PB0(ICP1/CLKO/PCINT0)_12") (pintype "bidirectional"))
      (node (ref "R9") (pin "1") (pinfunction "1_1") (pintype "passive"))
    )
    (net (code "50") (name "OR0") (class "Default")
      (node (ref "PAD12") (pin "1") (pinfunction "P_1") (pintype "passive"))
      (node (ref "PAD2") (pin "1") (pinfunction "P_1") (pintype "passive"))
      (node (ref "PAD22") (pin "1") (pinfunction "P_1") (pintype "passive"))
      (node (ref "PAD29") (pin "1") (pinfunction "P_1") (pintype "passive"))
      (node (ref "PAD37") (pin "1") (pinfunction "P_1") (pintype "passive"))
      (node (ref "R5") (pin "2") (pinfunction "2_2") (pintype "passive"))
    )
    (net (code "51") (name "OR1") (class "Default")
      (node (ref "PAD14") (pin "1") (pinfunction "P_1") (pintype "passive"))
      (node (ref "PAD24") (pin "1") (pinfunction "P_1") (pintype "passive"))
      (node (ref "PAD31") (pin "1") (pinfunction "P_1") (pintype "passive"))
      (node (ref "PAD39") (pin "1") (pinfunction "P_1") (pintype "passive"))
      (node (ref "PAD4") (pin "1") (pinfunction "P_1") (pintype "passive"))
      (node (ref "R6") (pin "2") (pinfunction "2_2") (pintype "passive"))
    )
    (net (code "52") (name "OR2") (class "Default")
      (node (ref "PAD16") (pin "1") (pinfunction "P_1") (pintype "passive"))
      (node (ref "PAD26") (pin "1") (pinfunction "P_1") (pintype "passive"))
      (node (ref "PAD33") (pin "1") (pinfunction "P_1") (pintype "passive"))
      (node (ref "PAD41") (pin "1") (pinfunction "P_1") (pintype "passive"))
      (node (ref "PAD6") (pin "1") (pinfunction "P_1") (pintype "passive"))
      (node (ref "R7") (pin "2") (pinfunction "2_2") (pintype "passive"))
    )
    (net (code "53") (name "OR3") (class "Default")
      (node (ref "PAD18") (pin "1") (pinfunction "P_1") (pintype "passive"))
      (node (ref "PAD28") (pin "1") (pinfunction "P_1") (pintype "passive"))
      (node (ref "PAD35") (pin "1") (pinfunction "P_1") (pintype "passive"))
      (node (ref "PAD43") (pin "1") (pinfunction "P_1") (pintype "passive"))
      (node (ref "PAD8") (pin "1") (pinfunction "P_1") (pintype "passive"))
      (node (ref "R8") (pin "2") (pinfunction "2_2") (pintype "passive"))
    )
    (net (code "54") (name "OR4") (class "Default")
      (node (ref "LD1") (pin "A") (pinfunction "A_A") (pintype "passive"))
      (node (ref "PAD10") (pin "1") (pinfunction "P_1") (pintype "passive"))
      (node (ref "PAD20") (pin "1") (pinfunction "P_1") (pintype "passive"))
      (node (ref "PAD45") (pin "1") (pinfunction "P_1") (pintype "passive"))
      (node (ref "R9") (pin "2") (pinfunction "2_2") (pintype "passive"))
    )
    (net (code "55") (name "RESET") (class "Default")
      (node (ref "IC1") (pin "29") (pinfunction "PC6(/RESET/PCINT14)_29") (pintype "bidirectional"))
      (node (ref "PAD47") (pin "1") (pinfunction "P_1") (pintype "passive"))
    )
    (net (code "56") (name "SCL") (class "Default")
      (node (ref "IC1") (pin "28") (pinfunction "PC5(ADC5/SCL/PCINT13)_28") (pintype "bidirectional"))
      (node (ref "PAD51") (pin "1") (pinfunction "P_1") (pintype "passive"))
    )
    (net (code "57") (name "SDA") (class "Default")
      (node (ref "IC1") (pin "27") (pinfunction "PC4(ADC4/SDA/PCINT12)_27") (pintype "bidirectional"))
      (node (ref "PAD50") (pin "1") (pinfunction "P_1") (pintype "passive"))
    )
    (net (code "58") (name "VCC") (class "Default")
      (node (ref "C1") (pin "1") (pinfunction "1_1") (pintype "passive"))
      (node (ref "C2") (pin "1") (pinfunction "1_1") (pintype "passive"))
      (node (ref "IC1") (pin "18") (pinfunction "AVCC_18") (pintype "passive"))
      (node (ref "IC1") (pin "20") (pinfunction "AREF_20") (pintype "passive"))
      (node (ref "IC1") (pin "4") (pinfunction "VCC_4") (pintype "power_in"))
      (node (ref "IC1") (pin "6") (pinfunction "VCC_6") (pintype "power_in"))
      (node (ref "PAD52") (pin "1") (pinfunction "P_1") (pintype "passive"))
    )
    (net (code "59") (name "unconnected-(S1-P1-Pad4)") (class "Default")
      (node (ref "S1") (pin "4") (pinfunction "P1_4") (pintype "passive"))
    )
    (net (code "60") (name "unconnected-(S1-S-Pad1)") (class "Default")
      (node (ref "S1") (pin "1") (pinfunction "S_1") (pintype "passive"))
    )
    (net (code "61") (name "unconnected-(S2-P1-Pad4)") (class "Default")
      (node (ref "S2") (pin "4") (pinfunction "P1_4") (pintype "passive"))
    )
    (net (code "62") (name "unconnected-(S2-S-Pad1)") (class "Default")
      (node (ref "S2") (pin "1") (pinfunction "S_1") (pintype "passive"))
    )
    (net (code "63") (name "unconnected-(S3-P1-Pad4)") (class "Default")
      (node (ref "S3") (pin "4") (pinfunction "P1_4") (pintype "passive"))
    )
    (net (code "64") (name "unconnected-(S3-S-Pad1)") (class "Default")
      (node (ref "S3") (pin "1") (pinfunction "S_1") (pintype "passive"))
    )
    (net (code "65") (name "unconnected-(S4-P1-Pad4)") (class "Default")
      (node (ref "S4") (pin "4") (pinfunction "P1_4") (pintype "passive"))
    )
    (net (code "66") (name "unconnected-(S4-S-Pad1)") (class "Default")
      (node (ref "S4") (pin "1") (pinfunction "S_1") (pintype "passive"))
    )
    (net (code "67") (name "unconnected-(S5-P1-Pad4)") (class "Default")
      (node (ref "S5") (pin "4") (pinfunction "P1_4") (pintype "passive"))
    )
    (net (code "68") (name "unconnected-(S5-S-Pad1)") (class "Default")
      (node (ref "S5") (pin "1") (pinfunction "S_1") (pintype "passive"))
    )
    (net (code "69") (name "unconnected-(S6-P1-Pad4)") (class "Default")
      (node (ref "S6") (pin "4") (pinfunction "P1_4") (pintype "passive"))
    )
    (net (code "70") (name "unconnected-(S6-S-Pad1)") (class "Default")
      (node (ref "S6") (pin "1") (pinfunction "S_1") (pintype "passive"))
    )
    (net (code "71") (name "unconnected-(S7-P1-Pad4)") (class "Default")
      (node (ref "S7") (pin "4") (pinfunction "P1_4") (pintype "passive"))
    )
    (net (code "72") (name "unconnected-(S7-S-Pad1)") (class "Default")
      (node (ref "S7") (pin "1") (pinfunction "S_1") (pintype "passive"))
    )
    (net (code "73") (name "unconnected-(S8-P1-Pad4)") (class "Default")
      (node (ref "S8") (pin "4") (pinfunction "P1_4") (pintype "passive"))
    )
    (net (code "74") (name "unconnected-(S8-S-Pad1)") (class "Default")
      (node (ref "S8") (pin "1") (pinfunction "S_1") (pintype "passive"))
    )
    (net (code "75") (name "unconnected-(S9-P1-Pad4)") (class "Default")
      (node (ref "S9") (pin "4") (pinfunction "P1_4") (pintype "passive"))
    )
    (net (code "76") (name "unconnected-(S9-S-Pad1)") (class "Default")
      (node (ref "S9") (pin "1") (pinfunction "S_1") (pintype "passive"))
    )
    (net (code "77") (name "unconnected-(S10-P1-Pad4)") (class "Default")
      (node (ref "S10") (pin "4") (pinfunction "P1_4") (pintype "passive"))
    )
    (net (code "78") (name "unconnected-(S10-S-Pad1)") (class "Default")
      (node (ref "S10") (pin "1") (pinfunction "S_1") (pintype "passive"))
    )
    (net (code "79") (name "unconnected-(S11-P1-Pad4)") (class "Default")
      (node (ref "S11") (pin "4") (pinfunction "P1_4") (pintype "passive"))
    )
    (net (code "80") (name "unconnected-(S11-S1-Pad2)") (class "Default")
      (node (ref "S11") (pin "2") (pinfunction "S1_2") (pintype "passive"))
    )
    (net (code "81") (name "unconnected-(S12-P-Pad3)") (class "Default")
      (node (ref "S12") (pin "3") (pinfunction "P_3") (pintype "passive"))
    )
    (net (code "82") (name "unconnected-(S12-S1-Pad2)") (class "Default")
      (node (ref "S12") (pin "2") (pinfunction "S1_2") (pintype "passive"))
    )
    (net (code "83") (name "unconnected-(S13-P1-Pad4)") (class "Default")
      (node (ref "S13") (pin "4") (pinfunction "P1_4") (pintype "passive"))
    )
    (net (code "84") (name "unconnected-(S13-S1-Pad2)") (class "Default")
      (node (ref "S13") (pin "2") (pinfunction "S1_2") (pintype "passive"))
    )
    (net (code "85") (name "unconnected-(S14-P-Pad3)") (class "Default")
      (node (ref "S14") (pin "3") (pinfunction "P_3") (pintype "passive"))
    )
    (net (code "86") (name "unconnected-(S14-S1-Pad2)") (class "Default")
      (node (ref "S14") (pin "2") (pinfunction "S1_2") (pintype "passive"))
    )
    (net (code "87") (name "unconnected-(S15-P1-Pad4)") (class "Default")
      (node (ref "S15") (pin "4") (pinfunction "P1_4") (pintype "passive"))
    )
    (net (code "88") (name "unconnected-(S15-S1-Pad2)") (class "Default")
      (node (ref "S15") (pin "2") (pinfunction "S1_2") (pintype "passive"))
    )
    (net (code "89") (name "unconnected-(S16-P-Pad3)") (class "Default")
      (node (ref "S16") (pin "3") (pinfunction "P_3") (pintype "passive"))
    )
    (net (code "90") (name "unconnected-(S16-S1-Pad2)") (class "Default")
      (node (ref "S16") (pin "2") (pinfunction "S1_2") (pintype "passive"))
    )
    (net (code "91") (name "unconnected-(S17-P1-Pad4)") (class "Default")
      (node (ref "S17") (pin "4") (pinfunction "P1_4") (pintype "passive"))
    )
    (net (code "92") (name "unconnected-(S17-S1-Pad2)") (class "Default")
      (node (ref "S17") (pin "2") (pinfunction "S1_2") (pintype "passive"))
    )
    (net (code "93") (name "unconnected-(S18-P-Pad3)") (class "Default")
      (node (ref "S18") (pin "3") (pinfunction "P_3") (pintype "passive"))
    )
    (net (code "94") (name "unconnected-(S18-S1-Pad2)") (class "Default")
      (node (ref "S18") (pin "2") (pinfunction "S1_2") (pintype "passive"))
    )
  )
)
